# Oddjobv3.net
KiCad netlist of a schematic drawn in EAGLE
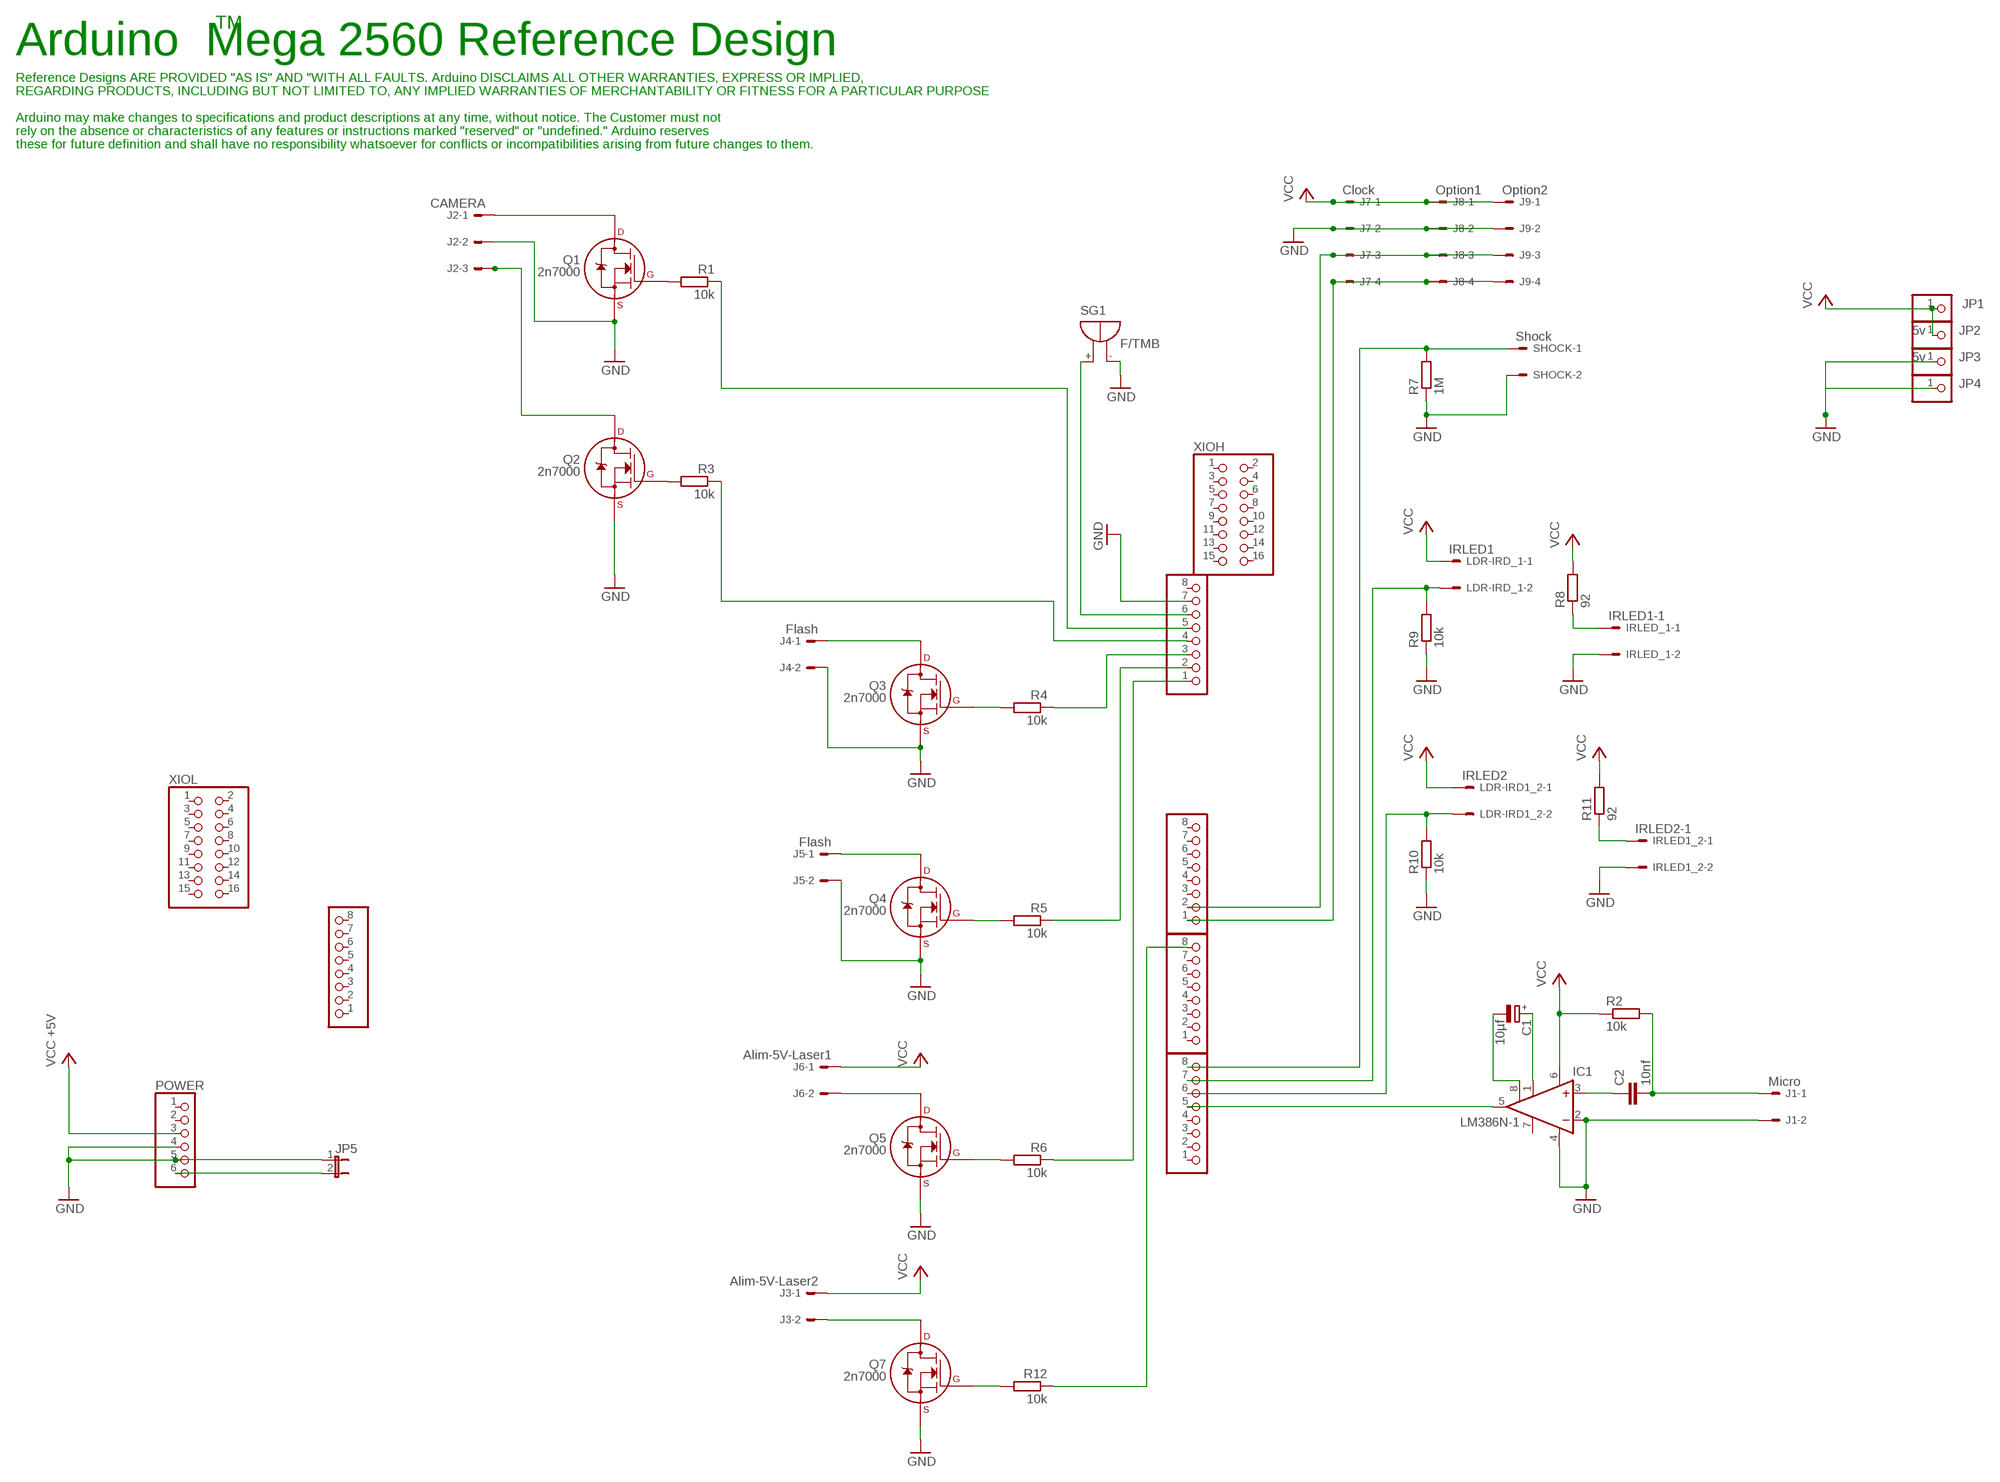
[diagram p0: schematic, sheet 1]

(export (version "E")
  (design (tool "Eeschema 10.0.6"))
  (components
    (comp (ref "ADCH")
      (value "PINHD-1X8")
      (footprint "eagle-import:1X08")
      (libsource (lib "eagle-import") (part "PINHD-1X8"))
    )
    (comp (ref "ADCL")
      (value "PINHD-1X8")
      (footprint "eagle-import:1X08")
      (libsource (lib "eagle-import") (part "PINHD-1X8"))
    )
    (comp (ref "C1")
      (value "10µf")
      (footprint "eagle-import:E2,5-6")
      (libsource (lib "eagle-import") (part "CPOL-EUE2.5-6"))
    )
    (comp (ref "C2")
      (value "10nf")
      (footprint "eagle-import:C050-025X075")
      (libsource (lib "eagle-import") (part "C-EU050-025X075"))
    )
    (comp (ref "COMMUNICATION")
      (value "PINHD-1X8")
      (footprint "eagle-import:1X08")
      (libsource (lib "eagle-import") (part "PINHD-1X8"))
    )
    (comp (ref "IC1")
      (value "LM386N-1")
      (footprint "eagle-import:DIL08")
      (libsource (lib "eagle-import") (part "LM386?-N1"))
    )
    (comp (ref "IRLED1_2")
      (value "IRLED2-1")
      (footprint "eagle-import:6410-02")
      (fields (field (name "OC_FARNELL") "unknown") (field (name "OC_NEWARK") "unknown"))
      (libsource (lib "eagle-import") (part "22-?-0227-2021"))
    )
    (comp (ref "IRLED_1")
      (value "IRLED1-1")
      (footprint "eagle-import:6410-02")
      (fields (field (name "OC_FARNELL") "unknown") (field (name "OC_NEWARK") "unknown"))
      (libsource (lib "eagle-import") (part "22-?-0227-2021"))
    )
    (comp (ref "J1")
      (value "Micro")
      (footprint "eagle-import:6410-02")
      (libsource (lib "eagle-import") (part "22-?-0227-2021"))
    )
    (comp (ref "J2")
      (value "CAMERA")
      (footprint "eagle-import:6410-03")
      (libsource (lib "eagle-import") (part "22-?-0327-2031"))
    )
    (comp (ref "J3")
      (value "Alim-5V-Laser2")
      (footprint "eagle-import:6410-02")
      (fields (field (name "OC_FARNELL") "unknown") (field (name "OC_NEWARK") "unknown"))
      (libsource (lib "eagle-import") (part "22-?-0227-2021"))
    )
    (comp (ref "J4")
      (value "Flash")
      (footprint "eagle-import:6410-02")
      (fields (field (name "OC_FARNELL") "unknown") (field (name "OC_NEWARK") "unknown"))
      (libsource (lib "eagle-import") (part "22-?-0227-2021"))
    )
    (comp (ref "J5")
      (value "Flash")
      (footprint "eagle-import:6410-02")
      (fields (field (name "OC_FARNELL") "unknown") (field (name "OC_NEWARK") "unknown"))
      (libsource (lib "eagle-import") (part "22-?-0227-2021"))
    )
    (comp (ref "J6")
      (value "Alim-5V-Laser1")
      (footprint "eagle-import:6410-02")
      (fields (field (name "OC_FARNELL") "unknown") (field (name "OC_NEWARK") "unknown"))
      (libsource (lib "eagle-import") (part "22-?-0227-2021"))
    )
    (comp (ref "J7")
      (value "Clock")
      (footprint "eagle-import:6410-04")
      (libsource (lib "eagle-import") (part "22-?-0427-2041"))
    )
    (comp (ref "J8")
      (value "Option1")
      (footprint "eagle-import:6410-04")
      (fields (field (name "OC_FARNELL") "unknown") (field (name "OC_NEWARK") "unknown"))
      (libsource (lib "eagle-import") (part "22-?-0427-2041"))
    )
    (comp (ref "J9")
      (value "Option2")
      (footprint "eagle-import:6410-04")
      (libsource (lib "eagle-import") (part "22-?-0427-2041"))
    )
    (comp (ref "JP1")
      (value "5v")
      (footprint "eagle-import:1X01")
      (libsource (lib "eagle-import") (part "PINHD-1X1"))
    )
    (comp (ref "JP2")
      (value "5v")
      (footprint "eagle-import:1X01")
      (libsource (lib "eagle-import") (part "PINHD-1X1"))
    )
    (comp (ref "JP3")
      (value "PINHD-1X1")
      (footprint "eagle-import:1X01")
      (libsource (lib "eagle-import") (part "PINHD-1X1"))
    )
    (comp (ref "JP4")
      (value "PINHD-1X1")
      (footprint "eagle-import:1X01")
      (libsource (lib "eagle-import") (part "PINHD-1X1"))
    )
    (comp (ref "JP5")
      (value "JP1E")
      (footprint "eagle-import:JP1")
      (libsource (lib "eagle-import") (part "JP1E"))
    )
    (comp (ref "LDR-IRD1_2")
      (value "IRLED2")
      (footprint "eagle-import:6410-02")
      (fields (field (name "OC_FARNELL") "unknown") (field (name "OC_NEWARK") "unknown"))
      (libsource (lib "eagle-import") (part "22-?-0227-2021"))
    )
    (comp (ref "LDR-IRD_1")
      (value "IRLED1")
      (footprint "eagle-import:6410-02")
      (fields (field (name "OC_FARNELL") "unknown") (field (name "OC_NEWARK") "unknown"))
      (libsource (lib "eagle-import") (part "22-?-0227-2021"))
    )
    (comp (ref "POWER")
      (value "PINHD-1X6")
      (footprint "eagle-import:1X06")
      (libsource (lib "eagle-import") (part "PINHD-1X6"))
    )
    (comp (ref "PWMH-NUMERIC")
      (value "PINHD-1X8")
      (footprint "eagle-import:1X08")
      (libsource (lib "eagle-import") (part "PINHD-1X8"))
    )
    (comp (ref "PWML")
      (value "PINHD-1X8")
      (footprint "eagle-import:1X08")
      (libsource (lib "eagle-import") (part "PINHD-1X8"))
    )
    (comp (ref "Q1")
      (value "2n7000")
      (footprint "eagle-import:TO-92")
      (libsource (lib "eagle-import") (part "2N700_TO920"))
    )
    (comp (ref "Q2")
      (value "2n7000")
      (footprint "eagle-import:TO-92")
      (libsource (lib "eagle-import") (part "2N700_TO920"))
    )
    (comp (ref "Q3")
      (value "2n7000")
      (footprint "eagle-import:TO-92")
      (libsource (lib "eagle-import") (part "2N700_TO920"))
    )
    (comp (ref "Q4")
      (value "2n7000")
      (footprint "eagle-import:TO-92")
      (libsource (lib "eagle-import") (part "2N700_TO920"))
    )
    (comp (ref "Q5")
      (value "2n7000")
      (footprint "eagle-import:TO-92")
      (libsource (lib "eagle-import") (part "2N700_TO920"))
    )
    (comp (ref "Q7")
      (value "2n7000")
      (footprint "eagle-import:TO-92")
      (libsource (lib "eagle-import") (part "2N700_TO920"))
    )
    (comp (ref "R1")
      (value "10k")
      (footprint "eagle-import:0207_7")
      (libsource (lib "eagle-import") (part "R-EU_0207/7"))
    )
    (comp (ref "R2")
      (value "10k")
      (footprint "eagle-import:0207_7")
      (libsource (lib "eagle-import") (part "R-EU_0207/7"))
    )
    (comp (ref "R3")
      (value "10k")
      (footprint "eagle-import:0207_7")
      (libsource (lib "eagle-import") (part "R-EU_0207/7"))
    )
    (comp (ref "R4")
      (value "10k")
      (footprint "eagle-import:0207_7")
      (libsource (lib "eagle-import") (part "R-EU_0207/7"))
    )
    (comp (ref "R5")
      (value "10k")
      (footprint "eagle-import:0207_7")
      (libsource (lib "eagle-import") (part "R-EU_0207/7"))
    )
    (comp (ref "R6")
      (value "10k")
      (footprint "eagle-import:0207_7")
      (libsource (lib "eagle-import") (part "R-EU_0207/7"))
    )
    (comp (ref "R7")
      (value "1M")
      (footprint "eagle-import:0207_7")
      (libsource (lib "eagle-import") (part "R-EU_0207/7"))
    )
    (comp (ref "R8")
      (value "92")
      (footprint "eagle-import:0207_7")
      (libsource (lib "eagle-import") (part "R-EU_0207/7"))
    )
    (comp (ref "R9")
      (value "10k")
      (footprint "eagle-import:0207_7")
      (libsource (lib "eagle-import") (part "R-EU_0207/7"))
    )
    (comp (ref "R10")
      (value "10k")
      (footprint "eagle-import:0207_7")
      (libsource (lib "eagle-import") (part "R-EU_0207/7"))
    )
    (comp (ref "R11")
      (value "92")
      (footprint "eagle-import:0207_7")
      (libsource (lib "eagle-import") (part "R-EU_0207/7"))
    )
    (comp (ref "R12")
      (value "10k")
      (footprint "eagle-import:0207_7")
      (libsource (lib "eagle-import") (part "R-EU_0207/7"))
    )
    (comp (ref "SG1")
      (value "F/TMB")
      (footprint "eagle-import:F_TMB")
      (libsource (lib "eagle-import") (part "F/TMB"))
    )
    (comp (ref "SHOCK")
      (value "Shock")
      (footprint "eagle-import:6410-02")
      (libsource (lib "eagle-import") (part "22-?-0227-2021"))
    )
    (comp (ref "XIOH")
      (value "PINHD-2X8")
      (footprint "eagle-import:2X08")
      (libsource (lib "eagle-import") (part "PINHD-2X8"))
    )
    (comp (ref "XIOL")
      (value "PINHD-2X8")
      (footprint "eagle-import:2X08")
      (libsource (lib "eagle-import") (part "PINHD-2X8"))
    )
  )
  (nets
    (net (code "1") (name "GND") (class "Default")
      (node (ref "IC1") (pin "2") (pinfunction "-IN_2") (pintype "input"))
      (node (ref "IC1") (pin "4") (pinfunction "GND_4") (pintype "power_in"))
      (node (ref "IRLED1_2") (pin "2") (pinfunction "S_2") (pintype "passive"))
      (node (ref "IRLED_1") (pin "2") (pinfunction "S_2") (pintype "passive"))
      (node (ref "J1") (pin "2") (pinfunction "S_2") (pintype "passive"))
      (node (ref "J2") (pin "2") (pinfunction "S_2") (pintype "passive"))
      (node (ref "J4") (pin "2") (pinfunction "S_2") (pintype "passive"))
      (node (ref "J5") (pin "2") (pinfunction "S_2") (pintype "passive"))
      (node (ref "J7") (pin "2") (pinfunction "S_2") (pintype "passive"))
      (node (ref "J8") (pin "2") (pinfunction "S_2") (pintype "passive"))
      (node (ref "J9") (pin "2") (pinfunction "S_2") (pintype "passive"))
      (node (ref "JP3") (pin "1") (pinfunction "1_1") (pintype "passive"))
      (node (ref "JP4") (pin "1") (pinfunction "1_1") (pintype "passive"))
      (node (ref "JP5") (pin "1") (pinfunction "1_1") (pintype "passive"))
      (node (ref "POWER") (pin "4") (pinfunction "4_4") (pintype "passive"))
      (node (ref "POWER") (pin "5") (pinfunction "5_5") (pintype "passive"))
      (node (ref "PWMH-NUMERIC") (pin "7") (pinfunction "7_7") (pintype "passive"))
      (node (ref "Q1") (pin "1") (pinfunction "S_1") (pintype "bidirectional"))
      (node (ref "Q2") (pin "1") (pinfunction "S_1") (pintype "bidirectional"))
      (node (ref "Q3") (pin "1") (pinfunction "S_1") (pintype "bidirectional"))
      (node (ref "Q4") (pin "1") (pinfunction "S_1") (pintype "bidirectional"))
      (node (ref "Q5") (pin "1") (pinfunction "S_1") (pintype "bidirectional"))
      (node (ref "Q7") (pin "1") (pinfunction "S_1") (pintype "bidirectional"))
      (node (ref "R10") (pin "1") (pinfunction "1_1") (pintype "passive"))
      (node (ref "R7") (pin "1") (pinfunction "1_1") (pintype "passive"))
      (node (ref "R9") (pin "1") (pinfunction "1_1") (pintype "passive"))
      (node (ref "SG1") (pin "-") (pinfunction "-_-") (pintype "passive"))
      (node (ref "SHOCK") (pin "2") (pinfunction "S_2") (pintype "passive"))
    )
    (net (code "2") (name "Net-(C1-Pad+)") (class "Default")
      (node (ref "C1") (pin "+") (pinfunction "+_+") (pintype "passive"))
      (node (ref "IC1") (pin "1") (pinfunction "GAIN_1") (pintype "passive"))
    )
    (net (code "3") (name "Net-(C1-Pad-)") (class "Default")
      (node (ref "C1") (pin "-") (pinfunction "-_-") (pintype "passive"))
      (node (ref "IC1") (pin "8") (pinfunction "GAIN_8") (pintype "passive"))
    )
    (net (code "4") (name "Net-(IC1-+IN)") (class "Default")
      (node (ref "C2") (pin "1") (pinfunction "1_1") (pintype "passive"))
      (node (ref "IC1") (pin "3") (pinfunction "+IN_3") (pintype "input"))
    )
    (net (code "5") (name "Net-(IC1-OUT)") (class "Default")
      (node (ref "ADCL") (pin "5") (pinfunction "5_5") (pintype "passive"))
      (node (ref "IC1") (pin "5") (pinfunction "OUT_5") (pintype "output"))
    )
    (net (code "6") (name "Net-(IRLED1_2A-S)") (class "Default")
      (node (ref "IRLED1_2") (pin "1") (pinfunction "S_1") (pintype "passive"))
      (node (ref "R11") (pin "1") (pinfunction "1_1") (pintype "passive"))
    )
    (net (code "7") (name "Net-(IRLED_1A-S)") (class "Default")
      (node (ref "IRLED_1") (pin "1") (pinfunction "S_1") (pintype "passive"))
      (node (ref "R8") (pin "1") (pinfunction "1_1") (pintype "passive"))
    )
    (net (code "8") (name "Net-(J1A-S)") (class "Default")
      (node (ref "C2") (pin "2") (pinfunction "2_2") (pintype "passive"))
      (node (ref "J1") (pin "1") (pinfunction "S_1") (pintype "passive"))
      (node (ref "R2") (pin "2") (pinfunction "2_2") (pintype "passive"))
    )
    (net (code "9") (name "Net-(J2A-S)") (class "Default")
      (node (ref "J2") (pin "1") (pinfunction "S_1") (pintype "passive"))
      (node (ref "Q1") (pin "3") (pinfunction "D_3") (pintype "bidirectional"))
    )
    (net (code "10") (name "Net-(J2C-S)") (class "Default")
      (node (ref "J2") (pin "3") (pinfunction "S_3") (pintype "passive"))
      (node (ref "Q2") (pin "3") (pinfunction "D_3") (pintype "bidirectional"))
    )
    (net (code "11") (name "Net-(J3B-S)") (class "Default")
      (node (ref "J3") (pin "2") (pinfunction "S_2") (pintype "passive"))
      (node (ref "Q7") (pin "3") (pinfunction "D_3") (pintype "bidirectional"))
    )
    (net (code "12") (name "Net-(J4A-S)") (class "Default")
      (node (ref "J4") (pin "1") (pinfunction "S_1") (pintype "passive"))
      (node (ref "Q3") (pin "3") (pinfunction "D_3") (pintype "bidirectional"))
    )
    (net (code "13") (name "Net-(J5A-S)") (class "Default")
      (node (ref "J5") (pin "1") (pinfunction "S_1") (pintype "passive"))
      (node (ref "Q4") (pin "3") (pinfunction "D_3") (pintype "bidirectional"))
    )
    (net (code "14") (name "Net-(J6B-S)") (class "Default")
      (node (ref "J6") (pin "2") (pinfunction "S_2") (pintype "passive"))
      (node (ref "Q5") (pin "3") (pinfunction "D_3") (pintype "bidirectional"))
    )
    (net (code "15") (name "Net-(J7C-S)") (class "Default")
      (node (ref "COMMUNICATION") (pin "2") (pinfunction "2_2") (pintype "passive"))
      (node (ref "J7") (pin "3") (pinfunction "S_3") (pintype "passive"))
      (node (ref "J8") (pin "3") (pinfunction "S_3") (pintype "passive"))
      (node (ref "J9") (pin "3") (pinfunction "S_3") (pintype "passive"))
    )
    (net (code "16") (name "Net-(J7D-S)") (class "Default")
      (node (ref "COMMUNICATION") (pin "1") (pinfunction "1_1") (pintype "passive"))
      (node (ref "J7") (pin "4") (pinfunction "S_4") (pintype "passive"))
      (node (ref "J8") (pin "4") (pinfunction "S_4") (pintype "passive"))
      (node (ref "J9") (pin "4") (pinfunction "S_4") (pintype "passive"))
    )
    (net (code "17") (name "Net-(JP5-Pad2)") (class "Default")
      (node (ref "JP5") (pin "2") (pinfunction "2_2") (pintype "passive"))
      (node (ref "POWER") (pin "6") (pinfunction "6_6") (pintype "passive"))
    )
    (net (code "18") (name "Net-(LDR-IRD1_2B-S)") (class "Default")
      (node (ref "ADCL") (pin "6") (pinfunction "6_6") (pintype "passive"))
      (node (ref "LDR-IRD1_2") (pin "2") (pinfunction "S_2") (pintype "passive"))
      (node (ref "R10") (pin "2") (pinfunction "2_2") (pintype "passive"))
    )
    (net (code "19") (name "Net-(LDR-IRD_1B-S)") (class "Default")
      (node (ref "ADCL") (pin "7") (pinfunction "7_7") (pintype "passive"))
      (node (ref "LDR-IRD_1") (pin "2") (pinfunction "S_2") (pintype "passive"))
      (node (ref "R9") (pin "2") (pinfunction "2_2") (pintype "passive"))
    )
    (net (code "20") (name "Net-(PWMH-NUMERIC-Pad1)") (class "Default")
      (node (ref "PWMH-NUMERIC") (pin "1") (pinfunction "1_1") (pintype "passive"))
      (node (ref "R6") (pin "1") (pinfunction "1_1") (pintype "passive"))
    )
    (net (code "21") (name "Net-(PWMH-NUMERIC-Pad2)") (class "Default")
      (node (ref "PWMH-NUMERIC") (pin "2") (pinfunction "2_2") (pintype "passive"))
      (node (ref "R5") (pin "1") (pinfunction "1_1") (pintype "passive"))
    )
    (net (code "22") (name "Net-(PWMH-NUMERIC-Pad3)") (class "Default")
      (node (ref "PWMH-NUMERIC") (pin "3") (pinfunction "3_3") (pintype "passive"))
      (node (ref "R4") (pin "1") (pinfunction "1_1") (pintype "passive"))
    )
    (net (code "23") (name "Net-(PWMH-NUMERIC-Pad4)") (class "Default")
      (node (ref "PWMH-NUMERIC") (pin "4") (pinfunction "4_4") (pintype "passive"))
      (node (ref "R3") (pin "1") (pinfunction "1_1") (pintype "passive"))
    )
    (net (code "24") (name "Net-(PWMH-NUMERIC-Pad5)") (class "Default")
      (node (ref "PWMH-NUMERIC") (pin "5") (pinfunction "5_5") (pintype "passive"))
      (node (ref "R1") (pin "1") (pinfunction "1_1") (pintype "passive"))
    )
    (net (code "25") (name "Net-(PWMH-NUMERIC-Pad6)") (class "Default")
      (node (ref "PWMH-NUMERIC") (pin "6") (pinfunction "6_6") (pintype "passive"))
      (node (ref "SG1") (pin "+") (pinfunction "+_+") (pintype "passive"))
    )
    (net (code "26") (name "Net-(PWML-Pad8)") (class "Default")
      (node (ref "PWML") (pin "8") (pinfunction "8_8") (pintype "passive"))
      (node (ref "R12") (pin "1") (pinfunction "1_1") (pintype "passive"))
    )
    (net (code "27") (name "Net-(Q1-G)") (class "Default")
      (node (ref "Q1") (pin "2") (pinfunction "G_2") (pintype "tri_state"))
      (node (ref "R1") (pin "2") (pinfunction "2_2") (pintype "passive"))
    )
    (net (code "28") (name "Net-(Q2-G)") (class "Default")
      (node (ref "Q2") (pin "2") (pinfunction "G_2") (pintype "tri_state"))
      (node (ref "R3") (pin "2") (pinfunction "2_2") (pintype "passive"))
    )
    (net (code "29") (name "Net-(Q3-G)") (class "Default")
      (node (ref "Q3") (pin "2") (pinfunction "G_2") (pintype "tri_state"))
      (node (ref "R4") (pin "2") (pinfunction "2_2") (pintype "passive"))
    )
    (net (code "30") (name "Net-(Q4-G)") (class "Default")
      (node (ref "Q4") (pin "2") (pinfunction "G_2") (pintype "tri_state"))
      (node (ref "R5") (pin "2") (pinfunction "2_2") (pintype "passive"))
    )
    (net (code "31") (name "Net-(Q5-G)") (class "Default")
      (node (ref "Q5") (pin "2") (pinfunction "G_2") (pintype "tri_state"))
      (node (ref "R6") (pin "2") (pinfunction "2_2") (pintype "passive"))
    )
    (net (code "32") (name "Net-(Q7-G)") (class "Default")
      (node (ref "Q7") (pin "2") (pinfunction "G_2") (pintype "tri_state"))
      (node (ref "R12") (pin "2") (pinfunction "2_2") (pintype "passive"))
    )
    (net (code "33") (name "Net-(SHOCKA-S)") (class "Default")
      (node (ref "ADCL") (pin "8") (pinfunction "8_8") (pintype "passive"))
      (node (ref "R7") (pin "2") (pinfunction "2_2") (pintype "passive"))
      (node (ref "SHOCK") (pin "1") (pinfunction "S_1") (pintype "passive"))
    )
    (net (code "34") (name "VCC") (class "Default")
      (node (ref "IC1") (pin "6") (pinfunction "VS_6") (pintype "power_in"))
      (node (ref "J3") (pin "1") (pinfunction "S_1") (pintype "passive"))
      (node (ref "J6") (pin "1") (pinfunction "S_1") (pintype "passive"))
      (node (ref "J7") (pin "1") (pinfunction "S_1") (pintype "passive"))
      (node (ref "J8") (pin "1") (pinfunction "S_1") (pintype "passive"))
      (node (ref "J9") (pin "1") (pinfunction "S_1") (pintype "passive"))
      (node (ref "JP1") (pin "1") (pinfunction "1_1") (pintype "passive"))
      (node (ref "JP2") (pin "1") (pinfunction "1_1") (pintype "passive"))
      (node (ref "LDR-IRD1_2") (pin "1") (pinfunction "S_1") (pintype "passive"))
      (node (ref "LDR-IRD_1") (pin "1") (pinfunction "S_1") (pintype "passive"))
      (node (ref "POWER") (pin "3") (pinfunction "3_3") (pintype "passive"))
      (node (ref "R11") (pin "2") (pinfunction "2_2") (pintype "passive"))
      (node (ref "R2") (pin "1") (pinfunction "1_1") (pintype "passive"))
      (node (ref "R8") (pin "2") (pinfunction "2_2") (pintype "passive"))
    )
    (net (code "35") (name "unconnected-(ADCH-Pad1)") (class "Default")
      (node (ref "ADCH") (pin "1") (pinfunction "1_1") (pintype "passive"))
    )
    (net (code "36") (name "unconnected-(ADCH-Pad2)") (class "Default")
      (node (ref "ADCH") (pin "2") (pinfunction "2_2") (pintype "passive"))
    )
    (net (code "37") (name "unconnected-(ADCH-Pad3)") (class "Default")
      (node (ref "ADCH") (pin "3") (pinfunction "3_3") (pintype "passive"))
    )
    (net (code "38") (name "unconnected-(ADCH-Pad4)") (class "Default")
      (node (ref "ADCH") (pin "4") (pinfunction "4_4") (pintype "passive"))
    )
    (net (code "39") (name "unconnected-(ADCH-Pad5)") (class "Default")
      (node (ref "ADCH") (pin "5") (pinfunction "5_5") (pintype "passive"))
    )
    (net (code "40") (name "unconnected-(ADCH-Pad6)") (class "Default")
      (node (ref "ADCH") (pin "6") (pinfunction "6_6") (pintype "passive"))
    )
    (net (code "41") (name "unconnected-(ADCH-Pad7)") (class "Default")
      (node (ref "ADCH") (pin "7") (pinfunction "7_7") (pintype "passive"))
    )
    (net (code "42") (name "unconnected-(ADCH-Pad8)") (class "Default")
      (node (ref "ADCH") (pin "8") (pinfunction "8_8") (pintype "passive"))
    )
    (net (code "43") (name "unconnected-(ADCL-Pad1)") (class "Default")
      (node (ref "ADCL") (pin "1") (pinfunction "1_1") (pintype "passive"))
    )
    (net (code "44") (name "unconnected-(ADCL-Pad2)") (class "Default")
      (node (ref "ADCL") (pin "2") (pinfunction "2_2") (pintype "passive"))
    )
    (net (code "45") (name "unconnected-(ADCL-Pad3)") (class "Default")
      (node (ref "ADCL") (pin "3") (pinfunction "3_3") (pintype "passive"))
    )
    (net (code "46") (name "unconnected-(ADCL-Pad4)") (class "Default")
      (node (ref "ADCL") (pin "4") (pinfunction "4_4") (pintype "passive"))
    )
    (net (code "47") (name "unconnected-(COMMUNICATION-Pad3)") (class "Default")
      (node (ref "COMMUNICATION") (pin "3") (pinfunction "3_3") (pintype "passive"))
    )
    (net (code "48") (name "unconnected-(COMMUNICATION-Pad4)") (class "Default")
      (node (ref "COMMUNICATION") (pin "4") (pinfunction "4_4") (pintype "passive"))
    )
    (net (code "49") (name "unconnected-(COMMUNICATION-Pad5)") (class "Default")
      (node (ref "COMMUNICATION") (pin "5") (pinfunction "5_5") (pintype "passive"))
    )
    (net (code "50") (name "unconnected-(COMMUNICATION-Pad6)") (class "Default")
      (node (ref "COMMUNICATION") (pin "6") (pinfunction "6_6") (pintype "passive"))
    )
    (net (code "51") (name "unconnected-(COMMUNICATION-Pad7)") (class "Default")
      (node (ref "COMMUNICATION") (pin "7") (pinfunction "7_7") (pintype "passive"))
    )
    (net (code "52") (name "unconnected-(COMMUNICATION-Pad8)") (class "Default")
      (node (ref "COMMUNICATION") (pin "8") (pinfunction "8_8") (pintype "passive"))
    )
    (net (code "53") (name "unconnected-(IC1-BYPASS-Pad7)") (class "Default")
      (node (ref "IC1") (pin "7") (pinfunction "BYPASS_7") (pintype "passive"))
    )
    (net (code "54") (name "unconnected-(POWER-Pad1)") (class "Default")
      (node (ref "POWER") (pin "1") (pinfunction "1_1") (pintype "passive"))
    )
    (net (code "55") (name "unconnected-(POWER-Pad2)") (class "Default")
      (node (ref "POWER") (pin "2") (pinfunction "2_2") (pintype "passive"))
    )
    (net (code "56") (name "unconnected-(PWMH-NUMERIC-Pad8)") (class "Default")
      (node (ref "PWMH-NUMERIC") (pin "8") (pinfunction "8_8") (pintype "passive"))
    )
    (net (code "57") (name "unconnected-(PWML-Pad1)") (class "Default")
      (node (ref "PWML") (pin "1") (pinfunction "1_1") (pintype "passive"))
    )
    (net (code "58") (name "unconnected-(PWML-Pad2)") (class "Default")
      (node (ref "PWML") (pin "2") (pinfunction "2_2") (pintype "passive"))
    )
    (net (code "59") (name "unconnected-(PWML-Pad3)") (class "Default")
      (node (ref "PWML") (pin "3") (pinfunction "3_3") (pintype "passive"))
    )
    (net (code "60") (name "unconnected-(PWML-Pad4)") (class "Default")
      (node (ref "PWML") (pin "4") (pinfunction "4_4") (pintype "passive"))
    )
    (net (code "61") (name "unconnected-(PWML-Pad5)") (class "Default")
      (node (ref "PWML") (pin "5") (pinfunction "5_5") (pintype "passive"))
    )
    (net (code "62") (name "unconnected-(PWML-Pad6)") (class "Default")
      (node (ref "PWML") (pin "6") (pinfunction "6_6") (pintype "passive"))
    )
    (net (code "63") (name "unconnected-(PWML-Pad7)") (class "Default")
      (node (ref "PWML") (pin "7") (pinfunction "7_7") (pintype "passive"))
    )
    (net (code "64") (name "unconnected-(XIOH-Pad1)") (class "Default")
      (node (ref "XIOH") (pin "1") (pinfunction "1_1") (pintype "passive"))
    )
    (net (code "65") (name "unconnected-(XIOH-Pad2)") (class "Default")
      (node (ref "XIOH") (pin "2") (pinfunction "2_2") (pintype "passive"))
    )
    (net (code "66") (name "unconnected-(XIOH-Pad3)") (class "Default")
      (node (ref "XIOH") (pin "3") (pinfunction "3_3") (pintype "passive"))
    )
    (net (code "67") (name "unconnected-(XIOH-Pad4)") (class "Default")
      (node (ref "XIOH") (pin "4") (pinfunction "4_4") (pintype "passive"))
    )
    (net (code "68") (name "unconnected-(XIOH-Pad5)") (class "Default")
      (node (ref "XIOH") (pin "5") (pinfunction "5_5") (pintype "passive"))
    )
    (net (code "69") (name "unconnected-(XIOH-Pad6)") (class "Default")
      (node (ref "XIOH") (pin "6") (pinfunction "6_6") (pintype "passive"))
    )
    (net (code "70") (name "unconnected-(XIOH-Pad7)") (class "Default")
      (node (ref "XIOH") (pin "7") (pinfunction "7_7") (pintype "passive"))
    )
    (net (code "71") (name "unconnected-(XIOH-Pad8)") (class "Default")
      (node (ref "XIOH") (pin "8") (pinfunction "8_8") (pintype "passive"))
    )
    (net (code "72") (name "unconnected-(XIOH-Pad9)") (class "Default")
      (node (ref "XIOH") (pin "9") (pinfunction "9_9") (pintype "passive"))
    )
    (net (code "73") (name "unconnected-(XIOH-Pad10)") (class "Default")
      (node (ref "XIOH") (pin "10") (pinfunction "10_10") (pintype "passive"))
    )
    (net (code "74") (name "unconnected-(XIOH-Pad11)") (class "Default")
      (node (ref "XIOH") (pin "11") (pinfunction "11_11") (pintype "passive"))
    )
    (net (code "75") (name "unconnected-(XIOH-Pad12)") (class "Default")
      (node (ref "XIOH") (pin "12") (pinfunction "12_12") (pintype "passive"))
    )
    (net (code "76") (name "unconnected-(XIOH-Pad13)") (class "Default")
      (node (ref "XIOH") (pin "13") (pinfunction "13_13") (pintype "passive"))
    )
    (net (code "77") (name "unconnected-(XIOH-Pad14)") (class "Default")
      (node (ref "XIOH") (pin "14") (pinfunction "14_14") (pintype "passive"))
    )
    (net (code "78") (name "unconnected-(XIOH-Pad15)") (class "Default")
      (node (ref "XIOH") (pin "15") (pinfunction "15_15") (pintype "passive"))
    )
    (net (code "79") (name "unconnected-(XIOH-Pad16)") (class "Default")
      (node (ref "XIOH") (pin "16") (pinfunction "16_16") (pintype "passive"))
    )
    (net (code "80") (name "unconnected-(XIOL-Pad1)") (class "Default")
      (node (ref "XIOL") (pin "1") (pinfunction "1_1") (pintype "passive"))
    )
    (net (code "81") (name "unconnected-(XIOL-Pad2)") (class "Default")
      (node (ref "XIOL") (pin "2") (pinfunction "2_2") (pintype "passive"))
    )
    (net (code "82") (name "unconnected-(XIOL-Pad3)") (class "Default")
      (node (ref "XIOL") (pin "3") (pinfunction "3_3") (pintype "passive"))
    )
    (net (code "83") (name "unconnected-(XIOL-Pad4)") (class "Default")
      (node (ref "XIOL") (pin "4") (pinfunction "4_4") (pintype "passive"))
    )
    (net (code "84") (name "unconnected-(XIOL-Pad5)") (class "Default")
      (node (ref "XIOL") (pin "5") (pinfunction "5_5") (pintype "passive"))
    )
    (net (code "85") (name "unconnected-(XIOL-Pad6)") (class "Default")
      (node (ref "XIOL") (pin "6") (pinfunction "6_6") (pintype "passive"))
    )
    (net (code "86") (name "unconnected-(XIOL-Pad7)") (class "Default")
      (node (ref "XIOL") (pin "7") (pinfunction "7_7") (pintype "passive"))
    )
    (net (code "87") (name "unconnected-(XIOL-Pad8)") (class "Default")
      (node (ref "XIOL") (pin "8") (pinfunction "8_8") (pintype "passive"))
    )
    (net (code "88") (name "unconnected-(XIOL-Pad9)") (class "Default")
      (node (ref "XIOL") (pin "9") (pinfunction "9_9") (pintype "passive"))
    )
    (net (code "89") (name "unconnected-(XIOL-Pad10)") (class "Default")
      (node (ref "XIOL") (pin "10") (pinfunction "10_10") (pintype "passive"))
    )
    (net (code "90") (name "unconnected-(XIOL-Pad11)") (class "Default")
      (node (ref "XIOL") (pin "11") (pinfunction "11_11") (pintype "passive"))
    )
    (net (code "91") (name "unconnected-(XIOL-Pad12)") (class "Default")
      (node (ref "XIOL") (pin "12") (pinfunction "12_12") (pintype "passive"))
    )
    (net (code "92") (name "unconnected-(XIOL-Pad13)") (class "Default")
      (node (ref "XIOL") (pin "13") (pinfunction "13_13") (pintype "passive"))
    )
    (net (code "93") (name "unconnected-(XIOL-Pad14)") (class "Default")
      (node (ref "XIOL") (pin "14") (pinfunction "14_14") (pintype "passive"))
    )
    (net (code "94") (name "unconnected-(XIOL-Pad15)") (class "Default")
      (node (ref "XIOL") (pin "15") (pinfunction "15_15") (pintype "passive"))
    )
    (net (code "95") (name "unconnected-(XIOL-Pad16)") (class "Default")
      (node (ref "XIOL") (pin "16") (pinfunction "16_16") (pintype "passive"))
    )
  )
)
